# spectrum_analyzer.net
KiCad netlist of a schematic drawn in EAGLE
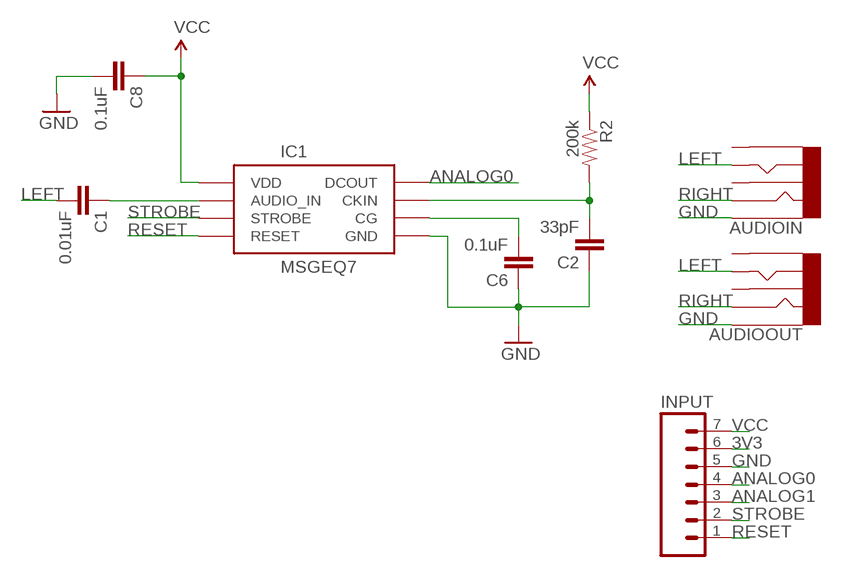
[diagram p0: schematic, sheet 1]

(export (version "E")
  (design (tool "Eeschema 10.0.6"))
  (components
    (comp (ref "AUDIOIN")
      (value "AUDIO-JACK2")
      (footprint "eagle-import:AUDIO-JACK")
      (libsource (lib "eagle-import") (part "AUDIO-JACK2"))
    )
    (comp (ref "AUDIOOUT")
      (value "AUDIO-JACK2")
      (footprint "eagle-import:AUDIO-JACK")
      (libsource (lib "eagle-import") (part "AUDIO-JACK2"))
    )
    (comp (ref "C1")
      (value "0.01uF")
      (footprint "eagle-import:0603-CAP")
      (libsource (lib "eagle-import") (part "CAP0603-CAP"))
    )
    (comp (ref "C2")
      (value "33pF")
      (footprint "eagle-import:0603-CAP")
      (libsource (lib "eagle-import") (part "CAP0603-CAP"))
    )
    (comp (ref "C6")
      (value "0.1uF")
      (footprint "eagle-import:0603-CAP")
      (libsource (lib "eagle-import") (part "CAP0603-CAP"))
    )
    (comp (ref "C8")
      (value "0.1uF")
      (footprint "eagle-import:0603-CAP")
      (libsource (lib "eagle-import") (part "CAP0603-CAP"))
    )
    (comp (ref "IC1")
      (value "MSGEQ7DIL")
      (footprint "eagle-import:DIL-08")
      (libsource (lib "eagle-import") (part "MSGEQ7DIL"))
    )
    (comp (ref "INPUT")
      (value "M07")
      (footprint "eagle-import:1X07")
      (libsource (lib "eagle-import") (part "M07"))
    )
    (comp (ref "R2")
      (value "200k")
      (footprint "eagle-import:0603-RES")
      (libsource (lib "eagle-import") (part "RESISTOR0603"))
    )
  )
  (nets
    (net (code "1") (name "/3V3") (class "Default")
      (node (ref "INPUT") (pin "6") (pinfunction "6_6") (pintype "passive"))
    )
    (net (code "2") (name "/ANALOG0") (class "Default")
      (node (ref "IC1") (pin "3") (pinfunction "DCOUT_3") (pintype "bidirectional"))
      (node (ref "INPUT") (pin "4") (pinfunction "4_4") (pintype "passive"))
    )
    (net (code "3") (name "/ANALOG1") (class "Default")
      (node (ref "INPUT") (pin "3") (pinfunction "3_3") (pintype "passive"))
    )
    (net (code "4") (name "/LEFT") (class "Default")
      (node (ref "AUDIOIN") (pin "5") (pinfunction "5_5") (pintype "bidirectional"))
      (node (ref "AUDIOOUT") (pin "5") (pinfunction "5_5") (pintype "bidirectional"))
      (node (ref "C1") (pin "2") (pinfunction "2_2") (pintype "passive"))
    )
    (net (code "5") (name "/RESET") (class "Default")
      (node (ref "IC1") (pin "7") (pinfunction "RESET_7") (pintype "input"))
      (node (ref "INPUT") (pin "1") (pinfunction "1_1") (pintype "passive"))
    )
    (net (code "6") (name "/RIGHT") (class "Default")
      (node (ref "AUDIOIN") (pin "2") (pinfunction "2_2") (pintype "bidirectional"))
      (node (ref "AUDIOOUT") (pin "2") (pinfunction "2_2") (pintype "bidirectional"))
    )
    (net (code "7") (name "/STROBE") (class "Default")
      (node (ref "IC1") (pin "4") (pinfunction "STROBE_4") (pintype "input"))
      (node (ref "INPUT") (pin "2") (pinfunction "2_2") (pintype "passive"))
    )
    (net (code "8") (name "GND") (class "Default")
      (node (ref "AUDIOIN") (pin "1") (pinfunction "1_1") (pintype "bidirectional"))
      (node (ref "AUDIOOUT") (pin "1") (pinfunction "1_1") (pintype "bidirectional"))
      (node (ref "C2") (pin "1") (pinfunction "1_1") (pintype "passive"))
      (node (ref "C6") (pin "1") (pinfunction "1_1") (pintype "passive"))
      (node (ref "C8") (pin "2") (pinfunction "2_2") (pintype "passive"))
      (node (ref "IC1") (pin "2") (pinfunction "GND_2") (pintype "bidirectional"))
      (node (ref "INPUT") (pin "5") (pinfunction "5_5") (pintype "passive"))
    )
    (net (code "9") (name "Net-(IC1-AUDIO_IN)") (class "Default")
      (node (ref "C1") (pin "1") (pinfunction "1_1") (pintype "passive"))
      (node (ref "IC1") (pin "5") (pinfunction "AUDIO_IN_5") (pintype "input"))
    )
    (net (code "10") (name "Net-(IC1-CG)") (class "Default")
      (node (ref "C6") (pin "2") (pinfunction "2_2") (pintype "passive"))
      (node (ref "IC1") (pin "6") (pinfunction "CG_6") (pintype "bidirectional"))
    )
    (net (code "11") (name "Net-(IC1-CKIN)") (class "Default")
      (node (ref "C2") (pin "2") (pinfunction "2_2") (pintype "passive"))
      (node (ref "IC1") (pin "8") (pinfunction "CKIN_8") (pintype "bidirectional"))
      (node (ref "R2") (pin "2") (pinfunction "2_2") (pintype "passive"))
    )
    (net (code "12") (name "VCC") (class "Default")
      (node (ref "C8") (pin "1") (pinfunction "1_1") (pintype "passive"))
      (node (ref "IC1") (pin "1") (pinfunction "VDD_1") (pintype "input"))
      (node (ref "INPUT") (pin "7") (pinfunction "7_7") (pintype "passive"))
      (node (ref "R2") (pin "1") (pinfunction "1_1") (pintype "passive"))
    )
    (net (code "13") (name "unconnected-(AUDIOIN-Pad3)") (class "Default")
      (node (ref "AUDIOIN") (pin "3") (pinfunction "3_3") (pintype "bidirectional"))
    )
    (net (code "14") (name "unconnected-(AUDIOIN-Pad4)") (class "Default")
      (node (ref "AUDIOIN") (pin "4") (pinfunction "4_4") (pintype "bidirectional"))
    )
    (net (code "15") (name "unconnected-(AUDIOOUT-Pad3)") (class "Default")
      (node (ref "AUDIOOUT") (pin "3") (pinfunction "3_3") (pintype "bidirectional"))
    )
    (net (code "16") (name "unconnected-(AUDIOOUT-Pad4)") (class "Default")
      (node (ref "AUDIOOUT") (pin "4") (pinfunction "4_4") (pintype "bidirectional"))
    )
  )
)
